# RFOUT_DaughterBoard.net
KiCad netlist of a schematic drawn in Altium Designer
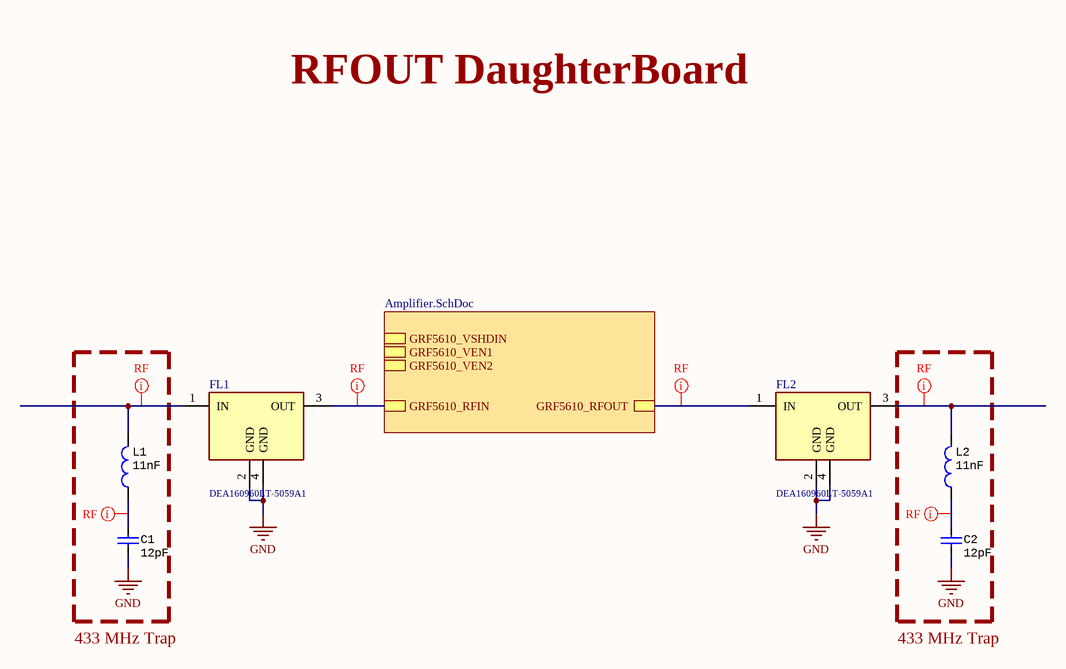
[diagram p0: RFOUT DaughterBoard.SchDoc]

(export (version "E")
  (design (tool "Eeschema 10.0.6"))
  (components
    (comp (ref "C1")
      (value "12pF")
      (footprint "CAP Ceramic SMD 0402")
      (description "CAP CER 12pF 50V C0G 0402")
      (fields
        (field (name "MANUFACTURER") "muRata")
        (field (name "MANUFACTURER PART NUMBER") "GJM1555C1H120FB01D")
      )
      (libsource (lib "RFOUT DaughterBoard") (part "CAP 0402 12pF 50V"))
    )
    (comp (ref "C2")
      (value "12pF")
      (footprint "CAP Ceramic SMD 0402")
      (description "CAP CER 12pF 50V C0G 0402")
      (fields
        (field (name "MANUFACTURER") "muRata")
        (field (name "MANUFACTURER PART NUMBER") "GJM1555C1H120FB01D")
      )
      (libsource (lib "RFOUT DaughterBoard") (part "CAP 0402 12pF 50V"))
    )
    (comp (ref "FL1")
      (value "DEA160960LT-5059A1")
      (footprint "DEA160960LT-5059A1")
      (description "Multilayer Low Pass Filter For 698 - 960 MHz")
      (fields (field (name "MANUFACTURER") "TDK"))
      (libsource (lib "RFOUT DaughterBoard") (part "DEA160960LT-5059A1"))
    )
    (comp (ref "FL2")
      (value "DEA160960LT-5059A1")
      (footprint "DEA160960LT-5059A1")
      (description "Multilayer Low Pass Filter For 698 - 960 MHz")
      (fields (field (name "MANUFACTURER") "TDK"))
      (libsource (lib "RFOUT DaughterBoard") (part "DEA160960LT-5059A1"))
    )
    (comp (ref "L1")
      (value "11nF")
      (footprint "IND SMD 0402")
      (description "FIXED IND 11nH 1.4A 83mΩ 0402")
      (fields
        (field (name "MANUFACTURER") "muRata")
        (field (name "MANUFACTURER PART NUMBER") "LQW15AN11NG8ZD")
      )
      (libsource (lib "RFOUT DaughterBoard") (part "IND 0402 11nH"))
    )
    (comp (ref "L2")
      (value "11nF")
      (footprint "IND SMD 0402")
      (description "FIXED IND 11nH 1.4A 83mΩ 0402")
      (fields
        (field (name "MANUFACTURER") "muRata")
        (field (name "MANUFACTURER PART NUMBER") "LQW15AN11NG8ZD")
      )
      (libsource (lib "RFOUT DaughterBoard") (part "IND 0402 11nH"))
    )
  )
  (nets
    (net (code "1") (name "/GRF5610_RFIN") (class "Default")
      (node (ref "FL1") (pin "3") (pinfunction "OUT_3") (pintype "passive"))
    )
    (net (code "2") (name "/GRF5610_RFOUT") (class "Default")
      (node (ref "FL2") (pin "1") (pinfunction "IN_1") (pintype "passive"))
    )
    (net (code "6") (name "GND") (class "Default")
      (node (ref "C1") (pin "2") (pinfunction "2_2") (pintype "passive"))
      (node (ref "C2") (pin "2") (pinfunction "2_2") (pintype "passive"))
      (node (ref "FL1") (pin "2") (pinfunction "GND_2") (pintype "passive"))
      (node (ref "FL1") (pin "4") (pinfunction "GND_4") (pintype "passive"))
      (node (ref "FL2") (pin "2") (pinfunction "GND_2") (pintype "passive"))
      (node (ref "FL2") (pin "4") (pinfunction "GND_4") (pintype "passive"))
    )
    (net (code "7") (name "Net-(C1-Pad1)") (class "Default")
      (node (ref "C1") (pin "1") (pinfunction "1_1") (pintype "passive"))
      (node (ref "L1") (pin "2") (pinfunction "2_2") (pintype "passive"))
    )
    (net (code "8") (name "Net-(C2-Pad1)") (class "Default")
      (node (ref "C2") (pin "1") (pinfunction "1_1") (pintype "passive"))
      (node (ref "L2") (pin "2") (pinfunction "2_2") (pintype "passive"))
    )
    (net (code "9") (name "Net-(FL1-IN)") (class "Default")
      (node (ref "FL1") (pin "1") (pinfunction "IN_1") (pintype "passive"))
      (node (ref "L1") (pin "1") (pinfunction "1_1") (pintype "passive"))
    )
    (net (code "10") (name "Net-(FL2-OUT)") (class "Default")
      (node (ref "FL2") (pin "3") (pinfunction "OUT_3") (pintype "passive"))
      (node (ref "L2") (pin "1") (pinfunction "1_1") (pintype "passive"))
    )
  )
)
